# Mood-Light-Perhaps.net
KiCad netlist of a schematic drawn in EAGLE
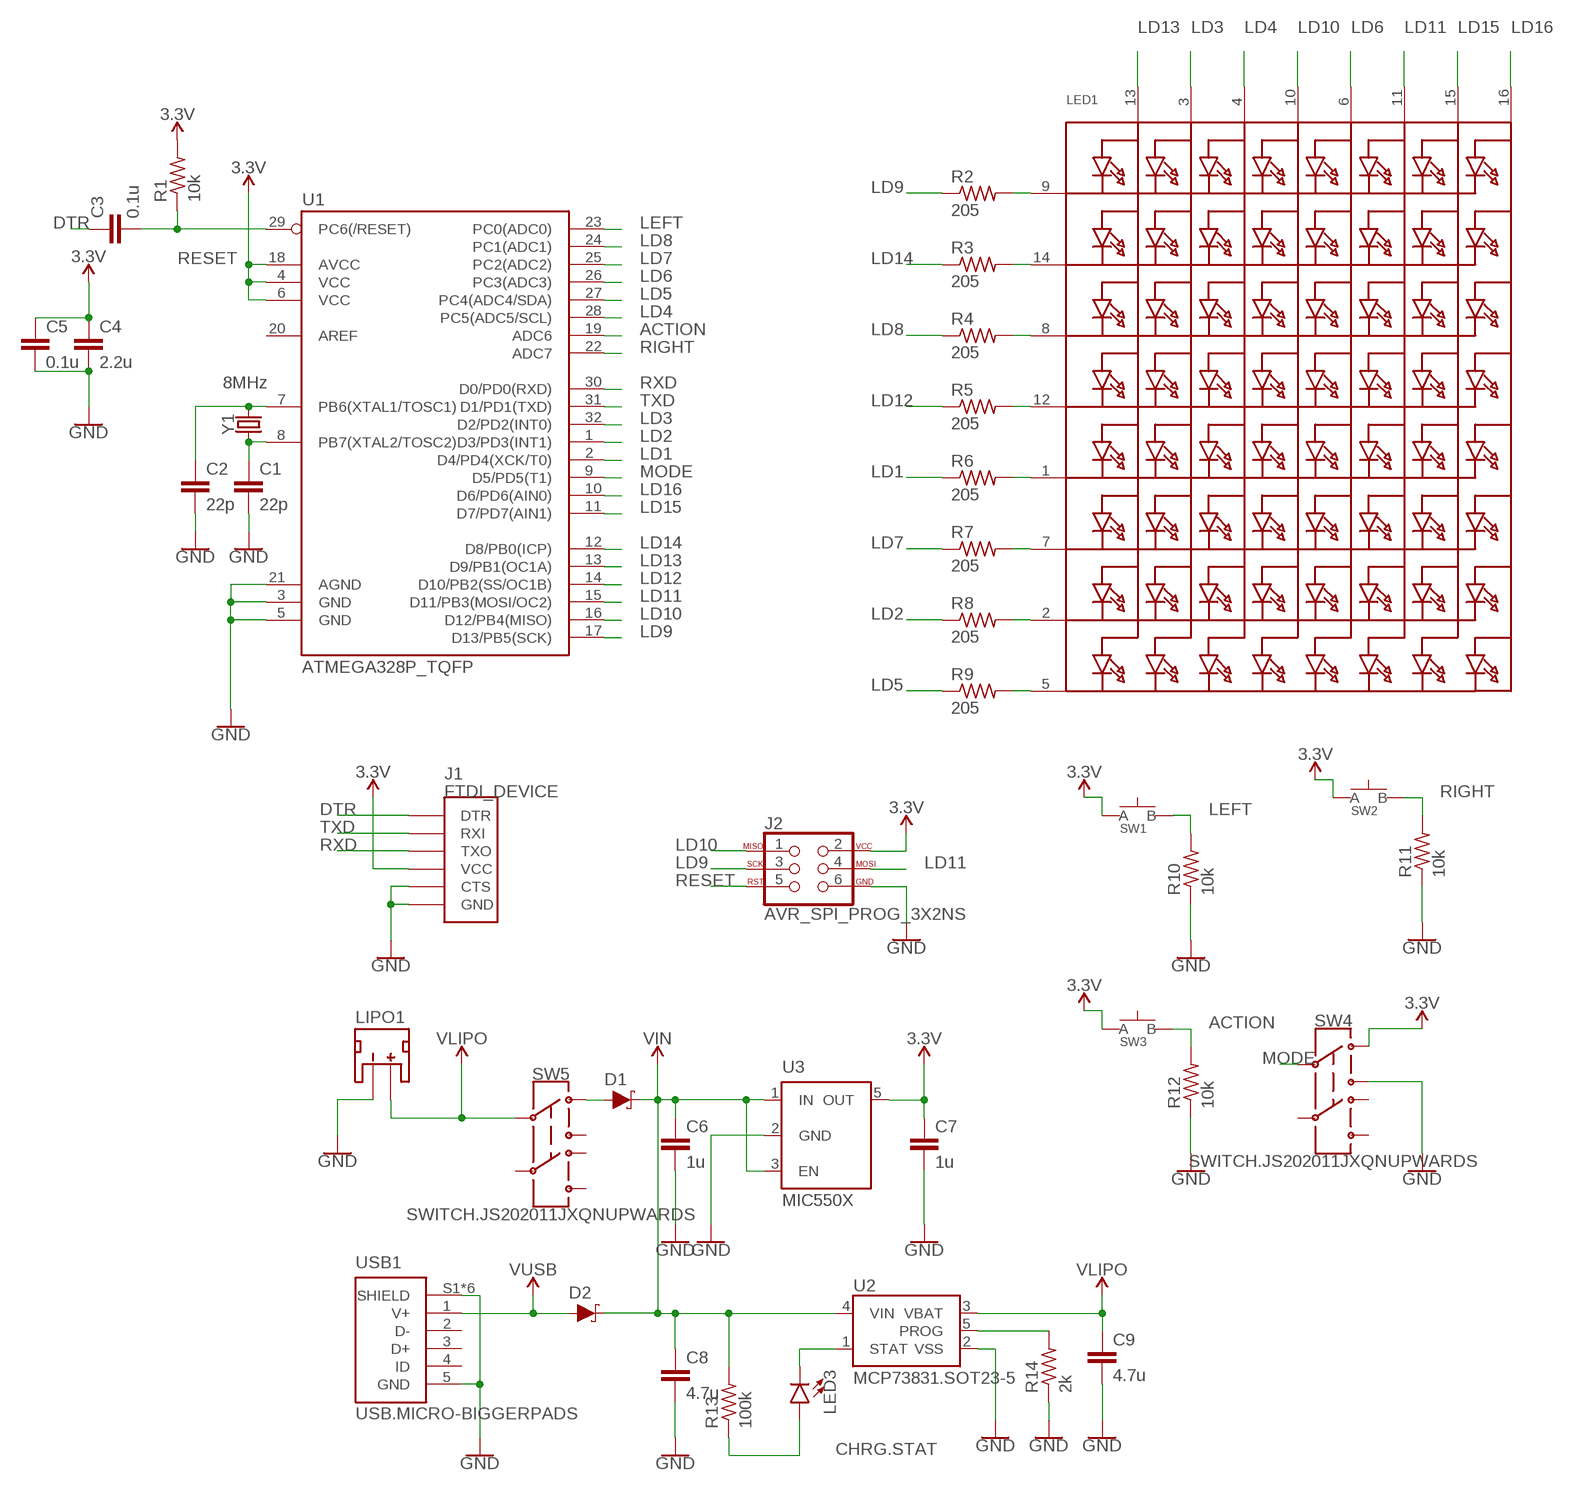
[diagram p0: schematic, sheet 1]

(export (version "E")
  (design (tool "Eeschema 10.0.6"))
  (components
    (comp (ref "C1")
      (value "22p")
      (footprint "eagle-import:C0603")
      (libsource (lib "eagle-import") (part "CAPACITOR0603"))
    )
    (comp (ref "C2")
      (value "22p")
      (footprint "eagle-import:C0603")
      (libsource (lib "eagle-import") (part "CAPACITOR0603"))
    )
    (comp (ref "C3")
      (value "0.1u")
      (footprint "eagle-import:C0603")
      (libsource (lib "eagle-import") (part "CAPACITOR0603"))
    )
    (comp (ref "C4")
      (value "2.2u")
      (footprint "eagle-import:C0603")
      (libsource (lib "eagle-import") (part "CAPACITOR0603"))
    )
    (comp (ref "C5")
      (value "0.1u")
      (footprint "eagle-import:C0603")
      (libsource (lib "eagle-import") (part "CAPACITOR0603"))
    )
    (comp (ref "C6")
      (value "1u")
      (footprint "eagle-import:C0603")
      (libsource (lib "eagle-import") (part "CAPACITOR0603"))
    )
    (comp (ref "C7")
      (value "1u")
      (footprint "eagle-import:C0603")
      (libsource (lib "eagle-import") (part "CAPACITOR0603"))
    )
    (comp (ref "C8")
      (value "4.7u")
      (footprint "eagle-import:C0603")
      (libsource (lib "eagle-import") (part "CAPACITOR0603"))
    )
    (comp (ref "C9")
      (value "4.7u")
      (footprint "eagle-import:C0603")
      (libsource (lib "eagle-import") (part "CAPACITOR0603"))
    )
    (comp (ref "D1")
      (value "SCHOTTKY-USC")
      (footprint "eagle-import:USC")
      (libsource (lib "eagle-import") (part "SCHOTTKY-USC"))
    )
    (comp (ref "D2")
      (value "SCHOTTKY-USC")
      (footprint "eagle-import:USC")
      (libsource (lib "eagle-import") (part "SCHOTTKY-USC"))
    )
    (comp (ref "J1")
      (value "FTDI_DEVICE")
      (footprint "eagle-import:FTDI_DEVICE")
      (libsource (lib "eagle-import") (part "FTDI_DEVICE"))
    )
    (comp (ref "J2")
      (value "AVR_SPI_PROG_3X2NS")
      (footprint "eagle-import:2X3-NS")
      (libsource (lib "eagle-import") (part "AVR_SPI_PROG_3X2NS"))
    )
    (comp (ref "LED1")
      (value "DOTMATRIX_8X8_ROWCATHODEM12A881UR")
      (footprint "eagle-import:DOTMATRIX_BL-M12A881UR")
      (libsource (lib "eagle-import") (part "DOTMATRIX_8X8_ROWCATHODEM12A881UR"))
    )
    (comp (ref "LED3")
      (value "LED0805")
      (footprint "eagle-import:LED-0805")
      (libsource (lib "eagle-import") (part "LED0805"))
    )
    (comp (ref "LIPO1")
      (value "JST_2MM_MALE")
      (footprint "eagle-import:JST-2-SMD")
      (libsource (lib "eagle-import") (part "JST_2MM_MALE"))
    )
    (comp (ref "R1")
      (value "10k")
      (footprint "eagle-import:R0603")
      (libsource (lib "eagle-import") (part "RESISTOR0603"))
    )
    (comp (ref "R2")
      (value "205")
      (footprint "eagle-import:R0603")
      (libsource (lib "eagle-import") (part "RESISTOR0603"))
    )
    (comp (ref "R3")
      (value "205")
      (footprint "eagle-import:R0603")
      (libsource (lib "eagle-import") (part "RESISTOR0603"))
    )
    (comp (ref "R4")
      (value "205")
      (footprint "eagle-import:R0603")
      (libsource (lib "eagle-import") (part "RESISTOR0603"))
    )
    (comp (ref "R5")
      (value "205")
      (footprint "eagle-import:R0603")
      (libsource (lib "eagle-import") (part "RESISTOR0603"))
    )
    (comp (ref "R6")
      (value "205")
      (footprint "eagle-import:R0603")
      (libsource (lib "eagle-import") (part "RESISTOR0603"))
    )
    (comp (ref "R7")
      (value "205")
      (footprint "eagle-import:R0603")
      (libsource (lib "eagle-import") (part "RESISTOR0603"))
    )
    (comp (ref "R8")
      (value "205")
      (footprint "eagle-import:R0603")
      (libsource (lib "eagle-import") (part "RESISTOR0603"))
    )
    (comp (ref "R9")
      (value "205")
      (footprint "eagle-import:R0603")
      (libsource (lib "eagle-import") (part "RESISTOR0603"))
    )
    (comp (ref "R10")
      (value "10k")
      (footprint "eagle-import:R0603")
      (libsource (lib "eagle-import") (part "RESISTOR0603"))
    )
    (comp (ref "R11")
      (value "10k")
      (footprint "eagle-import:R0603")
      (libsource (lib "eagle-import") (part "RESISTOR0603"))
    )
    (comp (ref "R12")
      (value "10k")
      (footprint "eagle-import:R0603")
      (libsource (lib "eagle-import") (part "RESISTOR0603"))
    )
    (comp (ref "R13")
      (value "100k")
      (footprint "eagle-import:R0603")
      (libsource (lib "eagle-import") (part "RESISTOR0603"))
    )
    (comp (ref "R14")
      (value "2k")
      (footprint "eagle-import:R0603")
      (libsource (lib "eagle-import") (part "RESISTOR0603"))
    )
    (comp (ref "SW1")
      (value "SPST.KT11P4SM34LFS")
      (footprint "eagle-import:SPST.KT11P4SM34LFS")
      (libsource (lib "eagle-import") (part "SPST.KT11P4SM34LFS"))
    )
    (comp (ref "SW2")
      (value "SPST.KT11P4SM34LFS")
      (footprint "eagle-import:SPST.KT11P4SM34LFS")
      (libsource (lib "eagle-import") (part "SPST.KT11P4SM34LFS"))
    )
    (comp (ref "SW3")
      (value "SPST.KT11P4SM34LFS")
      (footprint "eagle-import:SPST.KT11P4SM34LFS")
      (libsource (lib "eagle-import") (part "SPST.KT11P4SM34LFS"))
    )
    (comp (ref "SW4")
      (value "SWITCH.JS202011JXQNUPWARDS")
      (footprint "eagle-import:SWITCH.00")
      (libsource (lib "eagle-import") (part "SWITCH.JS202011JXQNUPWARDS"))
    )
    (comp (ref "SW5")
      (value "SWITCH.JS202011JXQNUPWARDS")
      (footprint "eagle-import:SWITCH.00")
      (libsource (lib "eagle-import") (part "SWITCH.JS202011JXQNUPWARDS"))
    )
    (comp (ref "U1")
      (value "ATMEGA328P_TQFP")
      (footprint "eagle-import:TQFP32-08")
      (libsource (lib "eagle-import") (part "ATMEGA328P_TQFP"))
    )
    (comp (ref "U2")
      (value "MCP73831.SOT23-5")
      (footprint "eagle-import:SOT23-5")
      (libsource (lib "eagle-import") (part "MCP73831.SOT23-5"))
    )
    (comp (ref "U3")
      (value "MIC550X")
      (footprint "eagle-import:SOT23-5")
      (libsource (lib "eagle-import") (part "MIC550X"))
    )
    (comp (ref "USB1")
      (value "USB.MICRO-BIGGERPADS")
      (footprint "eagle-import:USB-MICRO-01.BIGGERPADS")
      (libsource (lib "eagle-import") (part "USB.MICRO-BIGGERPADS"))
    )
    (comp (ref "Y1")
      (value "8MHz")
      (footprint "eagle-import:CA-301")
      (libsource (lib "eagle-import") (part "CRYSTAL-CA-310"))
    )
  )
  (nets
    (net (code "1") (name "/ACTION") (class "Default")
      (node (ref "R12") (pin "2") (pinfunction "2_2") (pintype "passive"))
      (node (ref "SW3") (pin "3") (pinfunction "B_3") (pintype "bidirectional"))
      (node (ref "SW3") (pin "4") (pinfunction "B_4") (pintype "bidirectional"))
      (node (ref "U1") (pin "19") (pinfunction "ADC6_19") (pintype "bidirectional"))
    )
    (net (code "2") (name "/CHRG.STAT") (class "Default")
      (node (ref "LED3") (pin "A") (pinfunction "A_A") (pintype "passive"))
      (node (ref "R13") (pin "1") (pinfunction "1_1") (pintype "passive"))
    )
    (net (code "3") (name "/DTR") (class "Default")
      (node (ref "C3") (pin "1") (pinfunction "1_1") (pintype "passive"))
      (node (ref "J1") (pin "DTR") (pinfunction "DTR_DTR") (pintype "bidirectional"))
    )
    (net (code "4") (name "/LD1") (class "Default")
      (node (ref "R6") (pin "1") (pinfunction "1_1") (pintype "passive"))
      (node (ref "U1") (pin "2") (pinfunction "D4/PD4(XCK/T0)_2") (pintype "bidirectional"))
    )
    (net (code "5") (name "/LD2") (class "Default")
      (node (ref "R8") (pin "1") (pinfunction "1_1") (pintype "passive"))
      (node (ref "U1") (pin "1") (pinfunction "D3/PD3(INT1)_1") (pintype "bidirectional"))
    )
    (net (code "6") (name "/LD3") (class "Default")
      (node (ref "LED1") (pin "3") (pinfunction "A2_3") (pintype "bidirectional"))
      (node (ref "U1") (pin "32") (pinfunction "D2/PD2(INT0)_32") (pintype "bidirectional"))
    )
    (net (code "7") (name "/LD4") (class "Default")
      (node (ref "LED1") (pin "4") (pinfunction "A3_4") (pintype "bidirectional"))
      (node (ref "U1") (pin "28") (pinfunction "PC5(ADC5/SCL)_28") (pintype "bidirectional"))
    )
    (net (code "8") (name "/LD5") (class "Default")
      (node (ref "R9") (pin "1") (pinfunction "1_1") (pintype "passive"))
      (node (ref "U1") (pin "27") (pinfunction "PC4(ADC4/SDA)_27") (pintype "bidirectional"))
    )
    (net (code "9") (name "/LD6") (class "Default")
      (node (ref "LED1") (pin "6") (pinfunction "A5_6") (pintype "bidirectional"))
      (node (ref "U1") (pin "26") (pinfunction "PC3(ADC3)_26") (pintype "bidirectional"))
    )
    (net (code "10") (name "/LD7") (class "Default")
      (node (ref "R7") (pin "1") (pinfunction "1_1") (pintype "passive"))
      (node (ref "U1") (pin "25") (pinfunction "PC2(ADC2)_25") (pintype "bidirectional"))
    )
    (net (code "11") (name "/LD8") (class "Default")
      (node (ref "R4") (pin "1") (pinfunction "1_1") (pintype "passive"))
      (node (ref "U1") (pin "24") (pinfunction "PC1(ADC1)_24") (pintype "bidirectional"))
    )
    (net (code "12") (name "/LD9") (class "Default")
      (node (ref "J2") (pin "3") (pinfunction "3_3") (pintype "passive"))
      (node (ref "R2") (pin "1") (pinfunction "1_1") (pintype "passive"))
      (node (ref "U1") (pin "17") (pinfunction "D13/PB5(SCK)_17") (pintype "bidirectional"))
    )
    (net (code "13") (name "/LD10") (class "Default")
      (node (ref "J2") (pin "1") (pinfunction "1_1") (pintype "passive"))
      (node (ref "LED1") (pin "10") (pinfunction "A4_10") (pintype "bidirectional"))
      (node (ref "U1") (pin "16") (pinfunction "D12/PB4(MISO)_16") (pintype "bidirectional"))
    )
    (net (code "14") (name "/LD11") (class "Default")
      (node (ref "J2") (pin "4") (pinfunction "4_4") (pintype "passive"))
      (node (ref "LED1") (pin "11") (pinfunction "A6_11") (pintype "bidirectional"))
      (node (ref "U1") (pin "15") (pinfunction "D11/PB3(MOSI/OC2)_15") (pintype "bidirectional"))
    )
    (net (code "15") (name "/LD12") (class "Default")
      (node (ref "R5") (pin "1") (pinfunction "1_1") (pintype "passive"))
      (node (ref "U1") (pin "14") (pinfunction "D10/PB2(SS/OC1B)_14") (pintype "bidirectional"))
    )
    (net (code "16") (name "/LD13") (class "Default")
      (node (ref "LED1") (pin "13") (pinfunction "A1_13") (pintype "bidirectional"))
      (node (ref "U1") (pin "13") (pinfunction "D9/PB1(OC1A)_13") (pintype "bidirectional"))
    )
    (net (code "17") (name "/LD14") (class "Default")
      (node (ref "R3") (pin "1") (pinfunction "1_1") (pintype "passive"))
      (node (ref "U1") (pin "12") (pinfunction "D8/PB0(ICP)_12") (pintype "bidirectional"))
    )
    (net (code "18") (name "/LD15") (class "Default")
      (node (ref "LED1") (pin "15") (pinfunction "A7_15") (pintype "bidirectional"))
      (node (ref "U1") (pin "11") (pinfunction "D7/PD7(AIN1)_11") (pintype "bidirectional"))
    )
    (net (code "19") (name "/LD16") (class "Default")
      (node (ref "LED1") (pin "16") (pinfunction "A8_16") (pintype "bidirectional"))
      (node (ref "U1") (pin "10") (pinfunction "D6/PD6(AIN0)_10") (pintype "bidirectional"))
    )
    (net (code "20") (name "/LEFT") (class "Default")
      (node (ref "R10") (pin "2") (pinfunction "2_2") (pintype "passive"))
      (node (ref "SW1") (pin "3") (pinfunction "B_3") (pintype "bidirectional"))
      (node (ref "SW1") (pin "4") (pinfunction "B_4") (pintype "bidirectional"))
      (node (ref "U1") (pin "23") (pinfunction "PC0(ADC0)_23") (pintype "bidirectional"))
    )
    (net (code "21") (name "/MODE") (class "Default")
      (node (ref "SW4") (pin "2") (pinfunction "2_2") (pintype "bidirectional"))
      (node (ref "U1") (pin "9") (pinfunction "D5/PD5(T1)_9") (pintype "bidirectional"))
    )
    (net (code "22") (name "/RESET") (class "Default")
      (node (ref "C3") (pin "2") (pinfunction "2_2") (pintype "passive"))
      (node (ref "J2") (pin "5") (pinfunction "5_5") (pintype "passive"))
      (node (ref "R1") (pin "1") (pinfunction "1_1") (pintype "passive"))
      (node (ref "U1") (pin "29") (pinfunction "PC6(/RESET)_29") (pintype "bidirectional"))
    )
    (net (code "23") (name "/RIGHT") (class "Default")
      (node (ref "R11") (pin "2") (pinfunction "2_2") (pintype "passive"))
      (node (ref "SW2") (pin "3") (pinfunction "B_3") (pintype "bidirectional"))
      (node (ref "SW2") (pin "4") (pinfunction "B_4") (pintype "bidirectional"))
      (node (ref "U1") (pin "22") (pinfunction "ADC7_22") (pintype "bidirectional"))
    )
    (net (code "24") (name "/RXD") (class "Default")
      (node (ref "J1") (pin "RXI") (pinfunction "TXO_RXI") (pintype "bidirectional"))
      (node (ref "U1") (pin "30") (pinfunction "D0/PD0(RXD)_30") (pintype "bidirectional"))
    )
    (net (code "25") (name "/TXD") (class "Default")
      (node (ref "J1") (pin "TXO") (pinfunction "RXI_TXO") (pintype "bidirectional"))
      (node (ref "U1") (pin "31") (pinfunction "D1/PD1(TXD)_31") (pintype "bidirectional"))
    )
    (net (code "26") (name "3.3V") (class "Default")
      (node (ref "C4") (pin "1") (pinfunction "1_1") (pintype "passive"))
      (node (ref "C5") (pin "1") (pinfunction "1_1") (pintype "passive"))
      (node (ref "C7") (pin "1") (pinfunction "1_1") (pintype "passive"))
      (node (ref "J1") (pin "VCC") (pinfunction "VCC_VCC") (pintype "bidirectional"))
      (node (ref "J2") (pin "2") (pinfunction "2_2") (pintype "passive"))
      (node (ref "R1") (pin "2") (pinfunction "2_2") (pintype "passive"))
      (node (ref "SW1") (pin "1") (pinfunction "A_1") (pintype "bidirectional"))
      (node (ref "SW1") (pin "2") (pinfunction "A_2") (pintype "bidirectional"))
      (node (ref "SW2") (pin "1") (pinfunction "A_1") (pintype "bidirectional"))
      (node (ref "SW2") (pin "2") (pinfunction "A_2") (pintype "bidirectional"))
      (node (ref "SW3") (pin "1") (pinfunction "A_1") (pintype "bidirectional"))
      (node (ref "SW3") (pin "2") (pinfunction "A_2") (pintype "bidirectional"))
      (node (ref "SW4") (pin "1") (pinfunction "1_1") (pintype "bidirectional"))
      (node (ref "U1") (pin "18") (pinfunction "AVCC_18") (pintype "bidirectional"))
      (node (ref "U1") (pin "4") (pinfunction "VCC_4") (pintype "bidirectional"))
      (node (ref "U1") (pin "6") (pinfunction "VCC_6") (pintype "bidirectional"))
      (node (ref "U3") (pin "5") (pinfunction "OUT_5") (pintype "bidirectional"))
    )
    (net (code "27") (name "GND") (class "Default")
      (node (ref "C1") (pin "2") (pinfunction "2_2") (pintype "passive"))
      (node (ref "C2") (pin "2") (pinfunction "2_2") (pintype "passive"))
      (node (ref "C4") (pin "2") (pinfunction "2_2") (pintype "passive"))
      (node (ref "C5") (pin "2") (pinfunction "2_2") (pintype "passive"))
      (node (ref "C6") (pin "2") (pinfunction "2_2") (pintype "passive"))
      (node (ref "C7") (pin "2") (pinfunction "2_2") (pintype "passive"))
      (node (ref "C8") (pin "2") (pinfunction "2_2") (pintype "passive"))
      (node (ref "C9") (pin "2") (pinfunction "2_2") (pintype "passive"))
      (node (ref "J1") (pin "CTS") (pinfunction "CTS_CTS") (pintype "bidirectional"))
      (node (ref "J1") (pin "GND") (pinfunction "GND_GND") (pintype "bidirectional"))
      (node (ref "J2") (pin "6") (pinfunction "6_6") (pintype "passive"))
      (node (ref "LIPO1") (pin "1") (pinfunction "-_1") (pintype "bidirectional"))
      (node (ref "R10") (pin "1") (pinfunction "1_1") (pintype "passive"))
      (node (ref "R11") (pin "1") (pinfunction "1_1") (pintype "passive"))
      (node (ref "R12") (pin "1") (pinfunction "1_1") (pintype "passive"))
      (node (ref "R14") (pin "1") (pinfunction "1_1") (pintype "passive"))
      (node (ref "SW4") (pin "3") (pinfunction "3_3") (pintype "bidirectional"))
      (node (ref "U1") (pin "21") (pinfunction "AGND_21") (pintype "bidirectional"))
      (node (ref "U1") (pin "3") (pinfunction "GND_3") (pintype "bidirectional"))
      (node (ref "U1") (pin "5") (pinfunction "GND_5") (pintype "bidirectional"))
      (node (ref "U2") (pin "2") (pinfunction "VSS_2") (pintype "power_in"))
      (node (ref "U3") (pin "2") (pinfunction "GND_2") (pintype "bidirectional"))
      (node (ref "USB1") (pin "5") (pinfunction "GND_5") (pintype "bidirectional"))
      (node (ref "USB1") (pin "S1") (pinfunction "SHIELD_S1") (pintype "bidirectional"))
      (node (ref "USB1") (pin "S2") (pinfunction "SHIELD_S2") (pintype "bidirectional"))
      (node (ref "USB1") (pin "S3") (pinfunction "SHIELD_S3") (pintype "bidirectional"))
      (node (ref "USB1") (pin "S4") (pinfunction "SHIELD_S4") (pintype "bidirectional"))
      (node (ref "USB1") (pin "S5") (pinfunction "SHIELD_S5") (pintype "bidirectional"))
      (node (ref "USB1") (pin "S6") (pinfunction "SHIELD_S6") (pintype "bidirectional"))
    )
    (net (code "28") (name "Net-(D1-A)") (class "Default")
      (node (ref "D1") (pin "+") (pinfunction "A_+") (pintype "passive"))
      (node (ref "SW5") (pin "1") (pinfunction "1_1") (pintype "bidirectional"))
    )
    (net (code "29") (name "Net-(LED1-K1)") (class "Default")
      (node (ref "LED1") (pin "9") (pinfunction "K1_9") (pintype "bidirectional"))
      (node (ref "R2") (pin "2") (pinfunction "2_2") (pintype "passive"))
    )
    (net (code "30") (name "Net-(LED1-K2)") (class "Default")
      (node (ref "LED1") (pin "14") (pinfunction "K2_14") (pintype "bidirectional"))
      (node (ref "R3") (pin "2") (pinfunction "2_2") (pintype "passive"))
    )
    (net (code "31") (name "Net-(LED1-K3)") (class "Default")
      (node (ref "LED1") (pin "8") (pinfunction "K3_8") (pintype "bidirectional"))
      (node (ref "R4") (pin "2") (pinfunction "2_2") (pintype "passive"))
    )
    (net (code "32") (name "Net-(LED1-K4)") (class "Default")
      (node (ref "LED1") (pin "12") (pinfunction "K4_12") (pintype "bidirectional"))
      (node (ref "R5") (pin "2") (pinfunction "2_2") (pintype "passive"))
    )
    (net (code "33") (name "Net-(LED1-K5)") (class "Default")
      (node (ref "LED1") (pin "1") (pinfunction "K5_1") (pintype "bidirectional"))
      (node (ref "R6") (pin "2") (pinfunction "2_2") (pintype "passive"))
    )
    (net (code "34") (name "Net-(LED1-K6)") (class "Default")
      (node (ref "LED1") (pin "7") (pinfunction "K6_7") (pintype "bidirectional"))
      (node (ref "R7") (pin "2") (pinfunction "2_2") (pintype "passive"))
    )
    (net (code "35") (name "Net-(LED1-K7)") (class "Default")
      (node (ref "LED1") (pin "2") (pinfunction "K7_2") (pintype "bidirectional"))
      (node (ref "R8") (pin "2") (pinfunction "2_2") (pintype "passive"))
    )
    (net (code "36") (name "Net-(LED1-K8)") (class "Default")
      (node (ref "LED1") (pin "5") (pinfunction "K8_5") (pintype "bidirectional"))
      (node (ref "R9") (pin "2") (pinfunction "2_2") (pintype "passive"))
    )
    (net (code "37") (name "Net-(U1-PB6(XTAL1{slash}TOSC1))") (class "Default")
      (node (ref "C2") (pin "1") (pinfunction "1_1") (pintype "passive"))
      (node (ref "U1") (pin "7") (pinfunction "PB6(XTAL1/TOSC1)_7") (pintype "bidirectional"))
      (node (ref "Y1") (pin "2") (pinfunction "2_2") (pintype "passive"))
    )
    (net (code "38") (name "Net-(U1-PB7(XTAL2{slash}TOSC2))") (class "Default")
      (node (ref "C1") (pin "1") (pinfunction "1_1") (pintype "passive"))
      (node (ref "U1") (pin "8") (pinfunction "PB7(XTAL2/TOSC2)_8") (pintype "bidirectional"))
      (node (ref "Y1") (pin "1") (pinfunction "1_1") (pintype "passive"))
    )
    (net (code "39") (name "Net-(U2-PROG)") (class "Default")
      (node (ref "R14") (pin "2") (pinfunction "2_2") (pintype "passive"))
      (node (ref "U2") (pin "5") (pinfunction "PROG_5") (pintype "input"))
    )
    (net (code "40") (name "Net-(U2-STAT)") (class "Default")
      (node (ref "LED3") (pin "C") (pinfunction "C_C") (pintype "passive"))
      (node (ref "U2") (pin "1") (pinfunction "STAT_1") (pintype "output"))
    )
    (net (code "41") (name "VIN") (class "Default")
      (node (ref "C6") (pin "1") (pinfunction "1_1") (pintype "passive"))
      (node (ref "C8") (pin "1") (pinfunction "1_1") (pintype "passive"))
      (node (ref "D1") (pin "-") (pinfunction "C_-") (pintype "passive"))
      (node (ref "D2") (pin "-") (pinfunction "C_-") (pintype "passive"))
      (node (ref "R13") (pin "2") (pinfunction "2_2") (pintype "passive"))
      (node (ref "U2") (pin "4") (pinfunction "VIN_4") (pintype "power_in"))
      (node (ref "U3") (pin "1") (pinfunction "IN_1") (pintype "bidirectional"))
      (node (ref "U3") (pin "3") (pinfunction "EN_3") (pintype "bidirectional"))
    )
    (net (code "42") (name "VLIPO") (class "Default")
      (node (ref "C9") (pin "1") (pinfunction "1_1") (pintype "passive"))
      (node (ref "LIPO1") (pin "2") (pinfunction "+_2") (pintype "bidirectional"))
      (node (ref "SW5") (pin "2") (pinfunction "2_2") (pintype "bidirectional"))
      (node (ref "U2") (pin "3") (pinfunction "VBAT_3") (pintype "power_in"))
    )
    (net (code "43") (name "VUSB") (class "Default")
      (node (ref "D2") (pin "+") (pinfunction "A_+") (pintype "passive"))
      (node (ref "USB1") (pin "1") (pinfunction "V+_1") (pintype "bidirectional"))
    )
    (net (code "44") (name "unconnected-(LIPO1-PAD1-PadNC1)") (class "Default")
      (node (ref "LIPO1") (pin "NC1") (pinfunction "PAD1_NC1") (pintype "bidirectional"))
    )
    (net (code "45") (name "unconnected-(LIPO1-PAD2-PadNC2)") (class "Default")
      (node (ref "LIPO1") (pin "NC2") (pinfunction "PAD2_NC2") (pintype "bidirectional"))
    )
    (net (code "46") (name "unconnected-(SW4-4-Pad5)") (class "Default")
      (node (ref "SW4") (pin "5") (pinfunction "4_5") (pintype "bidirectional"))
    )
    (net (code "47") (name "unconnected-(SW4-5-Pad6)") (class "Default")
      (node (ref "SW4") (pin "6") (pinfunction "5_6") (pintype "bidirectional"))
    )
    (net (code "48") (name "unconnected-(SW4-6-Pad7)") (class "Default")
      (node (ref "SW4") (pin "7") (pinfunction "6_7") (pintype "bidirectional"))
    )
    (net (code "49") (name "unconnected-(SW5-4-Pad5)") (class "Default")
      (node (ref "SW5") (pin "5") (pinfunction "4_5") (pintype "bidirectional"))
    )
    (net (code "50") (name "unconnected-(SW5-5-Pad6)") (class "Default")
      (node (ref "SW5") (pin "6") (pinfunction "5_6") (pintype "bidirectional"))
    )
    (net (code "51") (name "unconnected-(SW5-6-Pad7)") (class "Default")
      (node (ref "SW5") (pin "7") (pinfunction "6_7") (pintype "bidirectional"))
    )
    (net (code "52") (name "unconnected-(SW5-Pad3)") (class "Default")
      (node (ref "SW5") (pin "3") (pinfunction "3_3") (pintype "bidirectional"))
    )
    (net (code "53") (name "unconnected-(U1-AREF-Pad20)") (class "Default")
      (node (ref "U1") (pin "20") (pinfunction "AREF_20") (pintype "bidirectional"))
    )
    (net (code "54") (name "unconnected-(USB1-D+-Pad3)") (class "Default")
      (node (ref "USB1") (pin "3") (pinfunction "D+_3") (pintype "bidirectional"))
    )
    (net (code "55") (name "unconnected-(USB1-D--Pad2)") (class "Default")
      (node (ref "USB1") (pin "2") (pinfunction "D-_2") (pintype "bidirectional"))
    )
    (net (code "56") (name "unconnected-(USB1-ID-Pad4)") (class "Default")
      (node (ref "USB1") (pin "4") (pinfunction "ID_4") (pintype "bidirectional"))
    )
  )
)
